# x2-feed.net
KiCad netlist of a schematic drawn in EAGLE
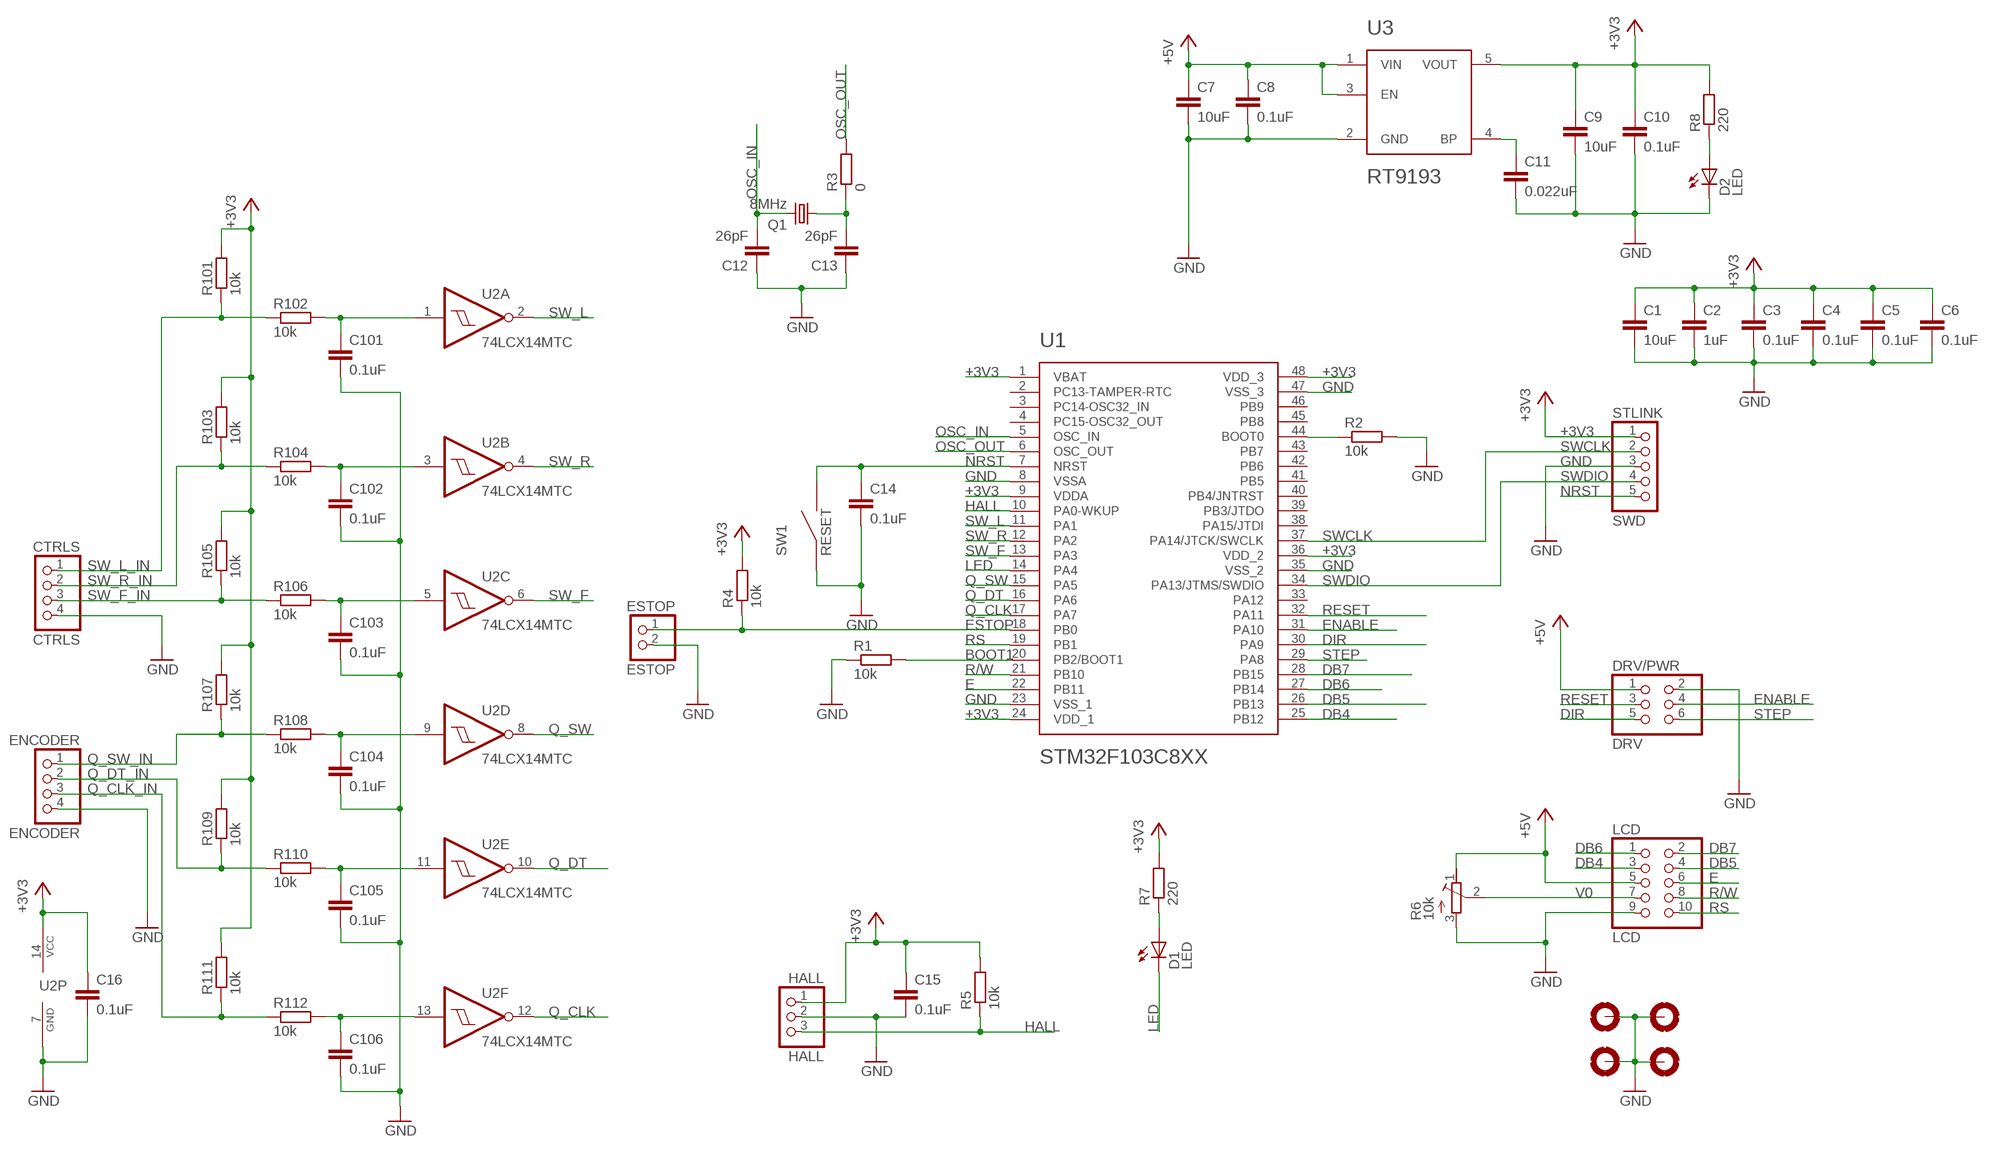
[diagram p0: schematic, sheet 1]

(export (version "E")
  (design (tool "Eeschema 10.0.6"))
  (components
    (comp (ref "C1")
      (value "10uF")
      (footprint "eagle-import:C2012")
      (libsource (lib "eagle-import") (part "CC2012"))
    )
    (comp (ref "C2")
      (value "1uF")
      (footprint "eagle-import:C1608")
      (libsource (lib "eagle-import") (part "CC1608"))
    )
    (comp (ref "C3")
      (value "0.1uF")
      (footprint "eagle-import:C1608")
      (libsource (lib "eagle-import") (part "CC1608"))
    )
    (comp (ref "C4")
      (value "0.1uF")
      (footprint "eagle-import:C1608")
      (libsource (lib "eagle-import") (part "CC1608"))
    )
    (comp (ref "C5")
      (value "0.1uF")
      (footprint "eagle-import:C1608")
      (libsource (lib "eagle-import") (part "CC1608"))
    )
    (comp (ref "C6")
      (value "0.1uF")
      (footprint "eagle-import:C1608")
      (libsource (lib "eagle-import") (part "CC1608"))
    )
    (comp (ref "C7")
      (value "10uF")
      (footprint "eagle-import:C2012")
      (libsource (lib "eagle-import") (part "CC2012"))
    )
    (comp (ref "C8")
      (value "0.1uF")
      (footprint "eagle-import:C1608")
      (libsource (lib "eagle-import") (part "CC1608"))
    )
    (comp (ref "C9")
      (value "10uF")
      (footprint "eagle-import:C2012")
      (libsource (lib "eagle-import") (part "CC2012"))
    )
    (comp (ref "C10")
      (value "0.1uF")
      (footprint "eagle-import:C1608")
      (libsource (lib "eagle-import") (part "CC1608"))
    )
    (comp (ref "C11")
      (value "0.022uF")
      (footprint "eagle-import:C1608")
      (libsource (lib "eagle-import") (part "CC1608"))
    )
    (comp (ref "C12")
      (value "26pF")
      (footprint "eagle-import:C1608")
      (libsource (lib "eagle-import") (part "CC1608"))
    )
    (comp (ref "C13")
      (value "26pF")
      (footprint "eagle-import:C1608")
      (libsource (lib "eagle-import") (part "CC1608"))
    )
    (comp (ref "C14")
      (value "0.1uF")
      (footprint "eagle-import:C1608")
      (libsource (lib "eagle-import") (part "CC1608"))
    )
    (comp (ref "C15")
      (value "0.1uF")
      (footprint "eagle-import:C1608")
      (libsource (lib "eagle-import") (part "CC1608"))
    )
    (comp (ref "C16")
      (value "0.1uF")
      (footprint "eagle-import:C1608")
      (libsource (lib "eagle-import") (part "CC1608"))
    )
    (comp (ref "C101")
      (value "0.1uF")
      (footprint "eagle-import:C1608")
      (libsource (lib "eagle-import") (part "CC1608"))
    )
    (comp (ref "C102")
      (value "0.1uF")
      (footprint "eagle-import:C1608")
      (libsource (lib "eagle-import") (part "CC1608"))
    )
    (comp (ref "C103")
      (value "0.1uF")
      (footprint "eagle-import:C1608")
      (libsource (lib "eagle-import") (part "CC1608"))
    )
    (comp (ref "C104")
      (value "0.1uF")
      (footprint "eagle-import:C1608")
      (libsource (lib "eagle-import") (part "CC1608"))
    )
    (comp (ref "C105")
      (value "0.1uF")
      (footprint "eagle-import:C1608")
      (libsource (lib "eagle-import") (part "CC1608"))
    )
    (comp (ref "C106")
      (value "0.1uF")
      (footprint "eagle-import:C1608")
      (libsource (lib "eagle-import") (part "CC1608"))
    )
    (comp (ref "CTRLS")
      (value "CTRLS")
      (footprint "eagle-import:1X04")
      (libsource (lib "eagle-import") (part "PINHD-1X4"))
    )
    (comp (ref "D1")
      (value "LED")
      (footprint "eagle-import:LED2012")
      (libsource (lib "eagle-import") (part "LED"))
    )
    (comp (ref "D2")
      (value "LED")
      (footprint "eagle-import:LED2012")
      (libsource (lib "eagle-import") (part "LED"))
    )
    (comp (ref "DRV/PWR")
      (value "DRV")
      (footprint "eagle-import:2X03")
      (libsource (lib "eagle-import") (part "PINHD-2X3"))
    )
    (comp (ref "ENCODER")
      (value "ENCODER")
      (footprint "eagle-import:1X04")
      (libsource (lib "eagle-import") (part "PINHD-1X4"))
    )
    (comp (ref "ESTOP")
      (value "ESTOP")
      (footprint "eagle-import:1X02")
      (libsource (lib "eagle-import") (part "PINHD-1X2"))
    )
    (comp (ref "H1")
      (value "MOUNT-PAD-ROUND2.8")
      (footprint "eagle-import:2,8-PAD")
      (libsource (lib "eagle-import") (part "MOUNT-PAD-ROUND2.8"))
    )
    (comp (ref "H2")
      (value "MOUNT-PAD-ROUND2.8")
      (footprint "eagle-import:2,8-PAD")
      (libsource (lib "eagle-import") (part "MOUNT-PAD-ROUND2.8"))
    )
    (comp (ref "H3")
      (value "MOUNT-PAD-ROUND2.8")
      (footprint "eagle-import:2,8-PAD")
      (libsource (lib "eagle-import") (part "MOUNT-PAD-ROUND2.8"))
    )
    (comp (ref "H4")
      (value "MOUNT-PAD-ROUND2.8")
      (footprint "eagle-import:2,8-PAD")
      (libsource (lib "eagle-import") (part "MOUNT-PAD-ROUND2.8"))
    )
    (comp (ref "HALL")
      (value "HALL")
      (footprint "eagle-import:5-103361-1")
      (libsource (lib "eagle-import") (part "5-103361-1"))
    )
    (comp (ref "LCD")
      (value "LCD")
      (footprint "eagle-import:2X05")
      (libsource (lib "eagle-import") (part "PINHD-2X5"))
    )
    (comp (ref "Q1")
      (value "8MHz")
      (footprint "eagle-import:HC49_S")
      (libsource (lib "eagle-import") (part "CRYSTAL9B"))
    )
    (comp (ref "R1")
      (value "10k")
      (footprint "eagle-import:R1608")
      (libsource (lib "eagle-import") (part "RR1608"))
    )
    (comp (ref "R2")
      (value "10k")
      (footprint "eagle-import:R1608")
      (libsource (lib "eagle-import") (part "RR1608"))
    )
    (comp (ref "R3")
      (value "0")
      (footprint "eagle-import:R1608")
      (libsource (lib "eagle-import") (part "RR1608"))
    )
    (comp (ref "R4")
      (value "10k")
      (footprint "eagle-import:R1608")
      (libsource (lib "eagle-import") (part "RR1608"))
    )
    (comp (ref "R5")
      (value "10k")
      (footprint "eagle-import:R1608")
      (libsource (lib "eagle-import") (part "RR1608"))
    )
    (comp (ref "R6")
      (value "10k")
      (footprint "eagle-import:RTRIMT93YA")
      (libsource (lib "eagle-import") (part "R-TRIMMT93YA"))
    )
    (comp (ref "R7")
      (value "220")
      (footprint "eagle-import:R1608")
      (libsource (lib "eagle-import") (part "RR1608"))
    )
    (comp (ref "R8")
      (value "220")
      (footprint "eagle-import:R1608")
      (libsource (lib "eagle-import") (part "RR1608"))
    )
    (comp (ref "R101")
      (value "10k")
      (footprint "eagle-import:R1608")
      (libsource (lib "eagle-import") (part "RR1608"))
    )
    (comp (ref "R102")
      (value "10k")
      (footprint "eagle-import:R1608")
      (libsource (lib "eagle-import") (part "RR1608"))
    )
    (comp (ref "R103")
      (value "10k")
      (footprint "eagle-import:R1608")
      (libsource (lib "eagle-import") (part "RR1608"))
    )
    (comp (ref "R104")
      (value "10k")
      (footprint "eagle-import:R1608")
      (libsource (lib "eagle-import") (part "RR1608"))
    )
    (comp (ref "R105")
      (value "10k")
      (footprint "eagle-import:R1608")
      (libsource (lib "eagle-import") (part "RR1608"))
    )
    (comp (ref "R106")
      (value "10k")
      (footprint "eagle-import:R1608")
      (libsource (lib "eagle-import") (part "RR1608"))
    )
    (comp (ref "R107")
      (value "10k")
      (footprint "eagle-import:R1608")
      (libsource (lib "eagle-import") (part "RR1608"))
    )
    (comp (ref "R108")
      (value "10k")
      (footprint "eagle-import:R1608")
      (libsource (lib "eagle-import") (part "RR1608"))
    )
    (comp (ref "R109")
      (value "10k")
      (footprint "eagle-import:R1608")
      (libsource (lib "eagle-import") (part "RR1608"))
    )
    (comp (ref "R110")
      (value "10k")
      (footprint "eagle-import:R1608")
      (libsource (lib "eagle-import") (part "RR1608"))
    )
    (comp (ref "R111")
      (value "10k")
      (footprint "eagle-import:R1608")
      (libsource (lib "eagle-import") (part "RR1608"))
    )
    (comp (ref "R112")
      (value "10k")
      (footprint "eagle-import:R1608")
      (libsource (lib "eagle-import") (part "RR1608"))
    )
    (comp (ref "STLINK")
      (value "SWD")
      (footprint "eagle-import:1X05")
      (libsource (lib "eagle-import") (part "PINHD-1X5"))
    )
    (comp (ref "SW1")
      (value "RESET")
      (footprint "eagle-import:PUSH")
      (libsource (lib "eagle-import") (part "PUSH"))
    )
    (comp (ref "U1")
      (value "STM32F103C8XX")
      (footprint "eagle-import:LQFP48-7X7MM")
      (libsource (lib "eagle-import") (part "STM32F103C8XX"))
    )
    (comp (ref "U2")
      (value "74LCX14MTC")
      (footprint "eagle-import:TSSOP14")
      (libsource (lib "eagle-import") (part "74LCX14MTC"))
    )
    (comp (ref "U3")
      (value "RT9193")
      (footprint "eagle-import:SOT23-5L")
      (libsource (lib "eagle-import") (part "RT9193"))
    )
  )
  (nets
    (net (code "1") (name "+3V3") (class "Default")
      (node (ref "C1") (pin "1") (pinfunction "1_1") (pintype "passive"))
      (node (ref "C10") (pin "1") (pinfunction "1_1") (pintype "passive"))
      (node (ref "C15") (pin "1") (pinfunction "1_1") (pintype "passive"))
      (node (ref "C16") (pin "1") (pinfunction "1_1") (pintype "passive"))
      (node (ref "C2") (pin "1") (pinfunction "1_1") (pintype "passive"))
      (node (ref "C3") (pin "1") (pinfunction "1_1") (pintype "passive"))
      (node (ref "C4") (pin "1") (pinfunction "1_1") (pintype "passive"))
      (node (ref "C5") (pin "1") (pinfunction "1_1") (pintype "passive"))
      (node (ref "C6") (pin "1") (pinfunction "1_1") (pintype "passive"))
      (node (ref "C9") (pin "1") (pinfunction "1_1") (pintype "passive"))
      (node (ref "HALL") (pin "1") (pinfunction "1_1") (pintype "passive"))
      (node (ref "R101") (pin "2") (pinfunction "2_2") (pintype "passive"))
      (node (ref "R103") (pin "2") (pinfunction "2_2") (pintype "passive"))
      (node (ref "R105") (pin "2") (pinfunction "2_2") (pintype "passive"))
      (node (ref "R107") (pin "2") (pinfunction "2_2") (pintype "passive"))
      (node (ref "R109") (pin "2") (pinfunction "2_2") (pintype "passive"))
      (node (ref "R111") (pin "2") (pinfunction "2_2") (pintype "passive"))
      (node (ref "R4") (pin "2") (pinfunction "2_2") (pintype "passive"))
      (node (ref "R5") (pin "2") (pinfunction "2_2") (pintype "passive"))
      (node (ref "R7") (pin "2") (pinfunction "2_2") (pintype "passive"))
      (node (ref "R8") (pin "2") (pinfunction "2_2") (pintype "passive"))
      (node (ref "STLINK") (pin "1") (pinfunction "1_1") (pintype "passive"))
      (node (ref "U1") (pin "1") (pinfunction "VBAT_1") (pintype "bidirectional"))
      (node (ref "U1") (pin "24") (pinfunction "VDD_1_24") (pintype "bidirectional"))
      (node (ref "U1") (pin "36") (pinfunction "VDD_2_36") (pintype "bidirectional"))
      (node (ref "U1") (pin "48") (pinfunction "VDD_3_48") (pintype "bidirectional"))
      (node (ref "U1") (pin "9") (pinfunction "VDDA_9") (pintype "bidirectional"))
      (node (ref "U2") (pin "14") (pinfunction "VCC_14") (pintype "power_in"))
      (node (ref "U3") (pin "5") (pinfunction "VOUT_5") (pintype "power_in"))
    )
    (net (code "2") (name "+5V") (class "Default")
      (node (ref "C7") (pin "1") (pinfunction "1_1") (pintype "passive"))
      (node (ref "C8") (pin "1") (pinfunction "1_1") (pintype "passive"))
      (node (ref "DRV/PWR") (pin "1") (pinfunction "1_1") (pintype "passive"))
      (node (ref "LCD") (pin "5") (pinfunction "5_5") (pintype "passive"))
      (node (ref "R6") (pin "1") (pinfunction "E_1") (pintype "passive"))
      (node (ref "U3") (pin "1") (pinfunction "VIN_1") (pintype "power_in"))
      (node (ref "U3") (pin "3") (pinfunction "EN_3") (pintype "bidirectional"))
    )
    (net (code "3") (name "/BOOT1") (class "Default")
      (node (ref "R1") (pin "2") (pinfunction "2_2") (pintype "passive"))
      (node (ref "U1") (pin "20") (pinfunction "PB2/BOOT1_20") (pintype "bidirectional"))
    )
    (net (code "4") (name "/DB4") (class "Default")
      (node (ref "LCD") (pin "3") (pinfunction "3_3") (pintype "passive"))
      (node (ref "U1") (pin "25") (pinfunction "PB12_25") (pintype "bidirectional"))
    )
    (net (code "5") (name "/DB5") (class "Default")
      (node (ref "LCD") (pin "4") (pinfunction "4_4") (pintype "passive"))
      (node (ref "U1") (pin "26") (pinfunction "PB13_26") (pintype "bidirectional"))
    )
    (net (code "6") (name "/DB6") (class "Default")
      (node (ref "LCD") (pin "1") (pinfunction "1_1") (pintype "passive"))
      (node (ref "U1") (pin "27") (pinfunction "PB14_27") (pintype "bidirectional"))
    )
    (net (code "7") (name "/DB7") (class "Default")
      (node (ref "LCD") (pin "2") (pinfunction "2_2") (pintype "passive"))
      (node (ref "U1") (pin "28") (pinfunction "PB15_28") (pintype "bidirectional"))
    )
    (net (code "8") (name "/DIR") (class "Default")
      (node (ref "DRV/PWR") (pin "5") (pinfunction "5_5") (pintype "passive"))
      (node (ref "U1") (pin "30") (pinfunction "PA9_30") (pintype "bidirectional"))
    )
    (net (code "9") (name "/E") (class "Default")
      (node (ref "LCD") (pin "6") (pinfunction "6_6") (pintype "passive"))
      (node (ref "U1") (pin "22") (pinfunction "PB11_22") (pintype "bidirectional"))
    )
    (net (code "10") (name "/ENABLE") (class "Default")
      (node (ref "DRV/PWR") (pin "4") (pinfunction "4_4") (pintype "passive"))
      (node (ref "U1") (pin "31") (pinfunction "PA10_31") (pintype "bidirectional"))
    )
    (net (code "11") (name "/ESTOP") (class "Default")
      (node (ref "ESTOP") (pin "1") (pinfunction "1_1") (pintype "passive"))
      (node (ref "R4") (pin "1") (pinfunction "1_1") (pintype "passive"))
      (node (ref "U1") (pin "18") (pinfunction "PB0_18") (pintype "bidirectional"))
    )
    (net (code "12") (name "/HALL") (class "Default")
      (node (ref "HALL") (pin "3") (pinfunction "3_3") (pintype "passive"))
      (node (ref "R5") (pin "1") (pinfunction "1_1") (pintype "passive"))
      (node (ref "U1") (pin "10") (pinfunction "PA0-WKUP_10") (pintype "bidirectional"))
    )
    (net (code "13") (name "/LED") (class "Default")
      (node (ref "D1") (pin "C") (pinfunction "C_C") (pintype "passive"))
      (node (ref "U1") (pin "14") (pinfunction "PA4_14") (pintype "bidirectional"))
    )
    (net (code "14") (name "/NRST") (class "Default")
      (node (ref "C14") (pin "1") (pinfunction "1_1") (pintype "passive"))
      (node (ref "STLINK") (pin "5") (pinfunction "5_5") (pintype "passive"))
      (node (ref "SW1") (pin "3") (pinfunction "2_3") (pintype "bidirectional"))
      (node (ref "SW1") (pin "4") (pinfunction "2_4") (pintype "bidirectional"))
      (node (ref "U1") (pin "7") (pinfunction "NRST_7") (pintype "bidirectional"))
    )
    (net (code "15") (name "/OSC_IN") (class "Default")
      (node (ref "C12") (pin "2") (pinfunction "2_2") (pintype "passive"))
      (node (ref "Q1") (pin "2") (pinfunction "2_2") (pintype "passive"))
      (node (ref "U1") (pin "5") (pinfunction "OSC_IN_5") (pintype "bidirectional"))
    )
    (net (code "16") (name "/OSC_OUT") (class "Default")
      (node (ref "R3") (pin "2") (pinfunction "2_2") (pintype "passive"))
      (node (ref "U1") (pin "6") (pinfunction "OSC_OUT_6") (pintype "bidirectional"))
    )
    (net (code "17") (name "/Q_CLK") (class "Default")
      (node (ref "U1") (pin "17") (pinfunction "PA7_17") (pintype "bidirectional"))
      (node (ref "U2") (pin "12") (pinfunction "O_12") (pintype "output"))
    )
    (net (code "18") (name "/Q_CLK_IN") (class "Default")
      (node (ref "ENCODER") (pin "3") (pinfunction "3_3") (pintype "passive"))
      (node (ref "R111") (pin "1") (pinfunction "1_1") (pintype "passive"))
      (node (ref "R112") (pin "1") (pinfunction "1_1") (pintype "passive"))
    )
    (net (code "19") (name "/Q_DT") (class "Default")
      (node (ref "U1") (pin "16") (pinfunction "PA6_16") (pintype "bidirectional"))
      (node (ref "U2") (pin "10") (pinfunction "O_10") (pintype "output"))
    )
    (net (code "20") (name "/Q_DT_IN") (class "Default")
      (node (ref "ENCODER") (pin "2") (pinfunction "2_2") (pintype "passive"))
      (node (ref "R109") (pin "1") (pinfunction "1_1") (pintype "passive"))
      (node (ref "R110") (pin "1") (pinfunction "1_1") (pintype "passive"))
    )
    (net (code "21") (name "/Q_SW") (class "Default")
      (node (ref "U1") (pin "15") (pinfunction "PA5_15") (pintype "bidirectional"))
      (node (ref "U2") (pin "8") (pinfunction "O_8") (pintype "output"))
    )
    (net (code "22") (name "/Q_SW_IN") (class "Default")
      (node (ref "ENCODER") (pin "1") (pinfunction "1_1") (pintype "passive"))
      (node (ref "R107") (pin "1") (pinfunction "1_1") (pintype "passive"))
      (node (ref "R108") (pin "1") (pinfunction "1_1") (pintype "passive"))
    )
    (net (code "23") (name "/RESET") (class "Default")
      (node (ref "DRV/PWR") (pin "3") (pinfunction "3_3") (pintype "passive"))
      (node (ref "U1") (pin "32") (pinfunction "PA11_32") (pintype "bidirectional"))
    )
    (net (code "24") (name "/RS") (class "Default")
      (node (ref "LCD") (pin "10") (pinfunction "10_10") (pintype "passive"))
      (node (ref "U1") (pin "19") (pinfunction "PB1_19") (pintype "bidirectional"))
    )
    (net (code "25") (name "/R{slash}W") (class "Default")
      (node (ref "LCD") (pin "8") (pinfunction "8_8") (pintype "passive"))
      (node (ref "U1") (pin "21") (pinfunction "PB10_21") (pintype "bidirectional"))
    )
    (net (code "26") (name "/STEP") (class "Default")
      (node (ref "DRV/PWR") (pin "6") (pinfunction "6_6") (pintype "passive"))
      (node (ref "U1") (pin "29") (pinfunction "PA8_29") (pintype "bidirectional"))
    )
    (net (code "27") (name "/SWCLK") (class "Default")
      (node (ref "STLINK") (pin "2") (pinfunction "2_2") (pintype "passive"))
      (node (ref "U1") (pin "37") (pinfunction "PA14/JTCK/SWCLK_37") (pintype "bidirectional"))
    )
    (net (code "28") (name "/SWDIO") (class "Default")
      (node (ref "STLINK") (pin "4") (pinfunction "4_4") (pintype "passive"))
      (node (ref "U1") (pin "34") (pinfunction "PA13/JTMS/SWDIO_34") (pintype "bidirectional"))
    )
    (net (code "29") (name "/SW_F") (class "Default")
      (node (ref "U1") (pin "13") (pinfunction "PA3_13") (pintype "bidirectional"))
      (node (ref "U2") (pin "6") (pinfunction "O_6") (pintype "output"))
    )
    (net (code "30") (name "/SW_F_IN") (class "Default")
      (node (ref "CTRLS") (pin "3") (pinfunction "3_3") (pintype "passive"))
      (node (ref "R105") (pin "1") (pinfunction "1_1") (pintype "passive"))
      (node (ref "R106") (pin "1") (pinfunction "1_1") (pintype "passive"))
    )
    (net (code "31") (name "/SW_L") (class "Default")
      (node (ref "U1") (pin "11") (pinfunction "PA1_11") (pintype "bidirectional"))
      (node (ref "U2") (pin "2") (pinfunction "O_2") (pintype "output"))
    )
    (net (code "32") (name "/SW_L_IN") (class "Default")
      (node (ref "CTRLS") (pin "1") (pinfunction "1_1") (pintype "passive"))
      (node (ref "R101") (pin "1") (pinfunction "1_1") (pintype "passive"))
      (node (ref "R102") (pin "1") (pinfunction "1_1") (pintype "passive"))
    )
    (net (code "33") (name "/SW_R") (class "Default")
      (node (ref "U1") (pin "12") (pinfunction "PA2_12") (pintype "bidirectional"))
      (node (ref "U2") (pin "4") (pinfunction "O_4") (pintype "output"))
    )
    (net (code "34") (name "/SW_R_IN") (class "Default")
      (node (ref "CTRLS") (pin "2") (pinfunction "2_2") (pintype "passive"))
      (node (ref "R103") (pin "1") (pinfunction "1_1") (pintype "passive"))
      (node (ref "R104") (pin "1") (pinfunction "1_1") (pintype "passive"))
    )
    (net (code "35") (name "/V0") (class "Default")
      (node (ref "LCD") (pin "7") (pinfunction "7_7") (pintype "passive"))
      (node (ref "R6") (pin "2") (pinfunction "S_2") (pintype "passive"))
    )
    (net (code "36") (name "GND") (class "Default")
      (node (ref "C1") (pin "2") (pinfunction "2_2") (pintype "passive"))
      (node (ref "C10") (pin "2") (pinfunction "2_2") (pintype "passive"))
      (node (ref "C101") (pin "2") (pinfunction "2_2") (pintype "passive"))
      (node (ref "C102") (pin "2") (pinfunction "2_2") (pintype "passive"))
      (node (ref "C103") (pin "2") (pinfunction "2_2") (pintype "passive"))
      (node (ref "C104") (pin "2") (pinfunction "2_2") (pintype "passive"))
      (node (ref "C105") (pin "2") (pinfunction "2_2") (pintype "passive"))
      (node (ref "C106") (pin "2") (pinfunction "2_2") (pintype "passive"))
      (node (ref "C11") (pin "2") (pinfunction "2_2") (pintype "passive"))
      (node (ref "C12") (pin "1") (pinfunction "1_1") (pintype "passive"))
      (node (ref "C13") (pin "1") (pinfunction "1_1") (pintype "passive"))
      (node (ref "C14") (pin "2") (pinfunction "2_2") (pintype "passive"))
      (node (ref "C15") (pin "2") (pinfunction "2_2") (pintype "passive"))
      (node (ref "C16") (pin "2") (pinfunction "2_2") (pintype "passive"))
      (node (ref "C2") (pin "2") (pinfunction "2_2") (pintype "passive"))
      (node (ref "C3") (pin "2") (pinfunction "2_2") (pintype "passive"))
      (node (ref "C4") (pin "2") (pinfunction "2_2") (pintype "passive"))
      (node (ref "C5") (pin "2") (pinfunction "2_2") (pintype "passive"))
      (node (ref "C6") (pin "2") (pinfunction "2_2") (pintype "passive"))
      (node (ref "C7") (pin "2") (pinfunction "2_2") (pintype "passive"))
      (node (ref "C8") (pin "2") (pinfunction "2_2") (pintype "passive"))
      (node (ref "C9") (pin "2") (pinfunction "2_2") (pintype "passive"))
      (node (ref "CTRLS") (pin "4") (pinfunction "4_4") (pintype "passive"))
      (node (ref "D2") (pin "C") (pinfunction "C_C") (pintype "passive"))
      (node (ref "DRV/PWR") (pin "2") (pinfunction "2_2") (pintype "passive"))
      (node (ref "ENCODER") (pin "4") (pinfunction "4_4") (pintype "passive"))
      (node (ref "ESTOP") (pin "2") (pinfunction "2_2") (pintype "passive"))
      (node (ref "H1") (pin "B2,8") (pinfunction "MOUNT_B2,8") (pintype "passive"))
      (node (ref "H2") (pin "B2,8") (pinfunction "MOUNT_B2,8") (pintype "passive"))
      (node (ref "H3") (pin "B2,8") (pinfunction "MOUNT_B2,8") (pintype "passive"))
      (node (ref "H4") (pin "B2,8") (pinfunction "MOUNT_B2,8") (pintype "passive"))
      (node (ref "HALL") (pin "2") (pinfunction "2_2") (pintype "passive"))
      (node (ref "LCD") (pin "9") (pinfunction "9_9") (pintype "passive"))
      (node (ref "R1") (pin "1") (pinfunction "1_1") (pintype "passive"))
      (node (ref "R2") (pin "2") (pinfunction "2_2") (pintype "passive"))
      (node (ref "R6") (pin "3") (pinfunction "A_3") (pintype "passive"))
      (node (ref "STLINK") (pin "3") (pinfunction "3_3") (pintype "passive"))
      (node (ref "SW1") (pin "1") (pinfunction "1_1") (pintype "bidirectional"))
      (node (ref "SW1") (pin "2") (pinfunction "1_2") (pintype "bidirectional"))
      (node (ref "U1") (pin "23") (pinfunction "VSS_1_23") (pintype "bidirectional"))
      (node (ref "U1") (pin "35") (pinfunction "VSS_2_35") (pintype "bidirectional"))
      (node (ref "U1") (pin "47") (pinfunction "VSS_3_47") (pintype "bidirectional"))
      (node (ref "U1") (pin "8") (pinfunction "VSSA_8") (pintype "bidirectional"))
      (node (ref "U2") (pin "7") (pinfunction "GND_7") (pintype "power_in"))
      (node (ref "U3") (pin "2") (pinfunction "GND_2") (pintype "power_in"))
    )
    (net (code "37") (name "Net-(C13-Pad2)") (class "Default")
      (node (ref "C13") (pin "2") (pinfunction "2_2") (pintype "passive"))
      (node (ref "Q1") (pin "1") (pinfunction "1_1") (pintype "passive"))
      (node (ref "R3") (pin "1") (pinfunction "1_1") (pintype "passive"))
    )
    (net (code "38") (name "Net-(D1-PadA)") (class "Default")
      (node (ref "D1") (pin "A") (pinfunction "A_A") (pintype "passive"))
      (node (ref "R7") (pin "1") (pinfunction "1_1") (pintype "passive"))
    )
    (net (code "39") (name "Net-(D2-PadA)") (class "Default")
      (node (ref "D2") (pin "A") (pinfunction "A_A") (pintype "passive"))
      (node (ref "R8") (pin "1") (pinfunction "1_1") (pintype "passive"))
    )
    (net (code "40") (name "Net-(U1-BOOT0)") (class "Default")
      (node (ref "R2") (pin "1") (pinfunction "1_1") (pintype "passive"))
      (node (ref "U1") (pin "44") (pinfunction "BOOT0_44") (pintype "bidirectional"))
    )
    (net (code "41") (name "Net-(U2A-I)") (class "Default")
      (node (ref "C101") (pin "1") (pinfunction "1_1") (pintype "passive"))
      (node (ref "R102") (pin "2") (pinfunction "2_2") (pintype "passive"))
      (node (ref "U2") (pin "1") (pinfunction "I_1") (pintype "input"))
    )
    (net (code "42") (name "Net-(U2B-I)") (class "Default")
      (node (ref "C102") (pin "1") (pinfunction "1_1") (pintype "passive"))
      (node (ref "R104") (pin "2") (pinfunction "2_2") (pintype "passive"))
      (node (ref "U2") (pin "3") (pinfunction "I_3") (pintype "input"))
    )
    (net (code "43") (name "Net-(U2C-I)") (class "Default")
      (node (ref "C103") (pin "1") (pinfunction "1_1") (pintype "passive"))
      (node (ref "R106") (pin "2") (pinfunction "2_2") (pintype "passive"))
      (node (ref "U2") (pin "5") (pinfunction "I_5") (pintype "input"))
    )
    (net (code "44") (name "Net-(U2D-I)") (class "Default")
      (node (ref "C104") (pin "1") (pinfunction "1_1") (pintype "passive"))
      (node (ref "R108") (pin "2") (pinfunction "2_2") (pintype "passive"))
      (node (ref "U2") (pin "9") (pinfunction "I_9") (pintype "input"))
    )
    (net (code "45") (name "Net-(U2E-I)") (class "Default")
      (node (ref "C105") (pin "1") (pinfunction "1_1") (pintype "passive"))
      (node (ref "R110") (pin "2") (pinfunction "2_2") (pintype "passive"))
      (node (ref "U2") (pin "11") (pinfunction "I_11") (pintype "input"))
    )
    (net (code "46") (name "Net-(U2F-I)") (class "Default")
      (node (ref "C106") (pin "1") (pinfunction "1_1") (pintype "passive"))
      (node (ref "R112") (pin "2") (pinfunction "2_2") (pintype "passive"))
      (node (ref "U2") (pin "13") (pinfunction "I_13") (pintype "input"))
    )
    (net (code "47") (name "Net-(U3-BP)") (class "Default")
      (node (ref "C11") (pin "1") (pinfunction "1_1") (pintype "passive"))
      (node (ref "U3") (pin "4") (pinfunction "BP_4") (pintype "bidirectional"))
    )
    (net (code "48") (name "unconnected-(U1-PA12-Pad33)") (class "Default")
      (node (ref "U1") (pin "33") (pinfunction "PA12_33") (pintype "bidirectional"))
    )
    (net (code "49") (name "unconnected-(U1-PA15{slash}JTDI-Pad38)") (class "Default")
      (node (ref "U1") (pin "38") (pinfunction "PA15/JTDI_38") (pintype "bidirectional"))
    )
    (net (code "50") (name "unconnected-(U1-PB3{slash}JTDO-Pad39)") (class "Default")
      (node (ref "U1") (pin "39") (pinfunction "PB3/JTDO_39") (pintype "bidirectional"))
    )
    (net (code "51") (name "unconnected-(U1-PB4{slash}JNTRST-Pad40)") (class "Default")
      (node (ref "U1") (pin "40") (pinfunction "PB4/JNTRST_40") (pintype "bidirectional"))
    )
    (net (code "52") (name "unconnected-(U1-PB5-Pad41)") (class "Default")
      (node (ref "U1") (pin "41") (pinfunction "PB5_41") (pintype "bidirectional"))
    )
    (net (code "53") (name "unconnected-(U1-PB6-Pad42)") (class "Default")
      (node (ref "U1") (pin "42") (pinfunction "PB6_42") (pintype "bidirectional"))
    )
    (net (code "54") (name "unconnected-(U1-PB7-Pad43)") (class "Default")
      (node (ref "U1") (pin "43") (pinfunction "PB7_43") (pintype "bidirectional"))
    )
    (net (code "55") (name "unconnected-(U1-PB8-Pad45)") (class "Default")
      (node (ref "U1") (pin "45") (pinfunction "PB8_45") (pintype "bidirectional"))
    )
    (net (code "56") (name "unconnected-(U1-PB9-Pad46)") (class "Default")
      (node (ref "U1") (pin "46") (pinfunction "PB9_46") (pintype "bidirectional"))
    )
    (net (code "57") (name "unconnected-(U1-PC13-TAMPER-RTC-Pad2)") (class "Default")
      (node (ref "U1") (pin "2") (pinfunction "PC13-TAMPER-RTC_2") (pintype "bidirectional"))
    )
    (net (code "58") (name "unconnected-(U1-PC14-OSC32_IN-Pad3)") (class "Default")
      (node (ref "U1") (pin "3") (pinfunction "PC14-OSC32_IN_3") (pintype "bidirectional"))
    )
    (net (code "59") (name "unconnected-(U1-PC15-OSC32_OUT-Pad4)") (class "Default")
      (node (ref "U1") (pin "4") (pinfunction "PC15-OSC32_OUT_4") (pintype "bidirectional"))
    )
  )
)
